# PushButtonGreen.net
KiCad netlist of a schematic drawn in Altium Designer
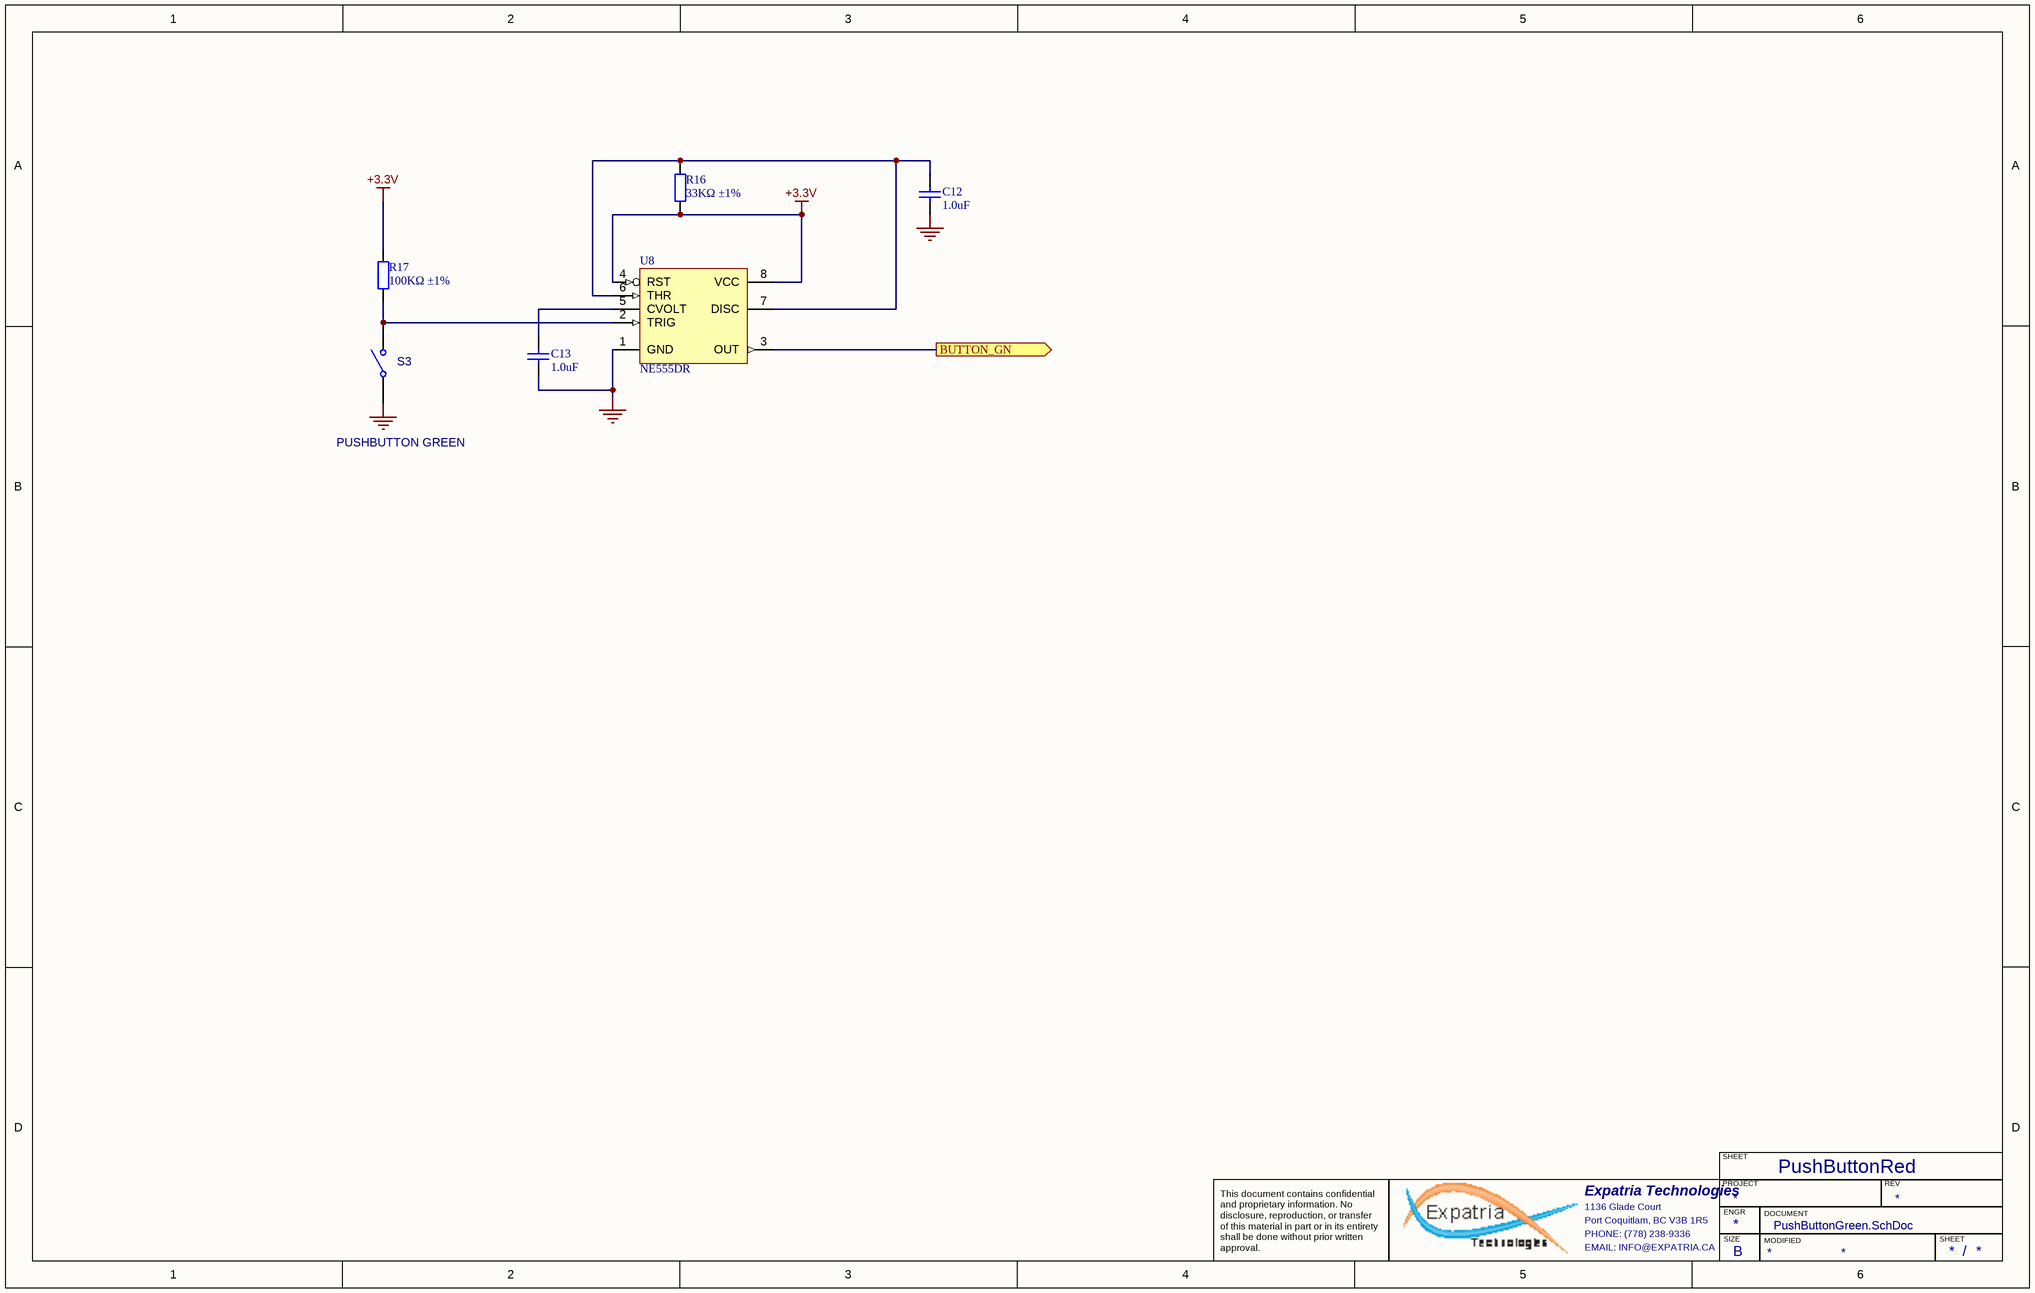
[diagram p0: PushButtonGreen.SchDoc]

(export (version "E")
  (design (tool "Eeschema 10.0.6"))
  (components
    (comp (ref "C12")
      (value "1.0uF")
      (footprint "0402_C")
      (description "Chip capacitor")
      (fields
        (field (name "MANUFACTURER") "Samsung Electro-Mechanics")
        (field (name "PARTNUMBER") "CL05A105KA5NQNC")
      )
      (libsource (lib "Cap") (part "0402 1.0uF (105) 10% 25V"))
    )
    (comp (ref "C13")
      (value "1.0uF")
      (footprint "0402_C")
      (description "Chip capacitor")
      (fields
        (field (name "MANUFACTURER") "Samsung Electro-Mechanics")
        (field (name "PARTNUMBER") "CL05A105KA5NQNC")
      )
      (libsource (lib "Cap") (part "0402 1.0uF (105) 10% 25V"))
    )
    (comp (ref "R16")
      (value "33KΩ ±1%")
      (footprint "0402_R")
      (description "Chip resistor")
      (fields (field (name "MANUFACTURER") "Uniroyal Elec") (field (name "PARTNUMBER") "0402WGF3302TCE"))
      (libsource (lib "RES") (part "0402 33K (3302) 1%"))
    )
    (comp (ref "R17")
      (value "100KΩ ±1%")
      (footprint "0402_R")
      (description "Chip resistor")
      (fields (field (name "MANUFACTURER") "Uniroyal Elec") (field (name "PARTNUMBER") "0402WGF1003TCE"))
      (libsource (lib "RES") (part "0402 100K (1003) 1%"))
    )
    (comp (ref "S3")
      (value "PUSHBUTTON GREEN")
      (footprint "D6C10F1LFS _GREEN")
      (description "SWITCH PUSH SPST-NO 0.1A 32V RED")
      (libsource (lib "bluebell") (part "D6R40 F1 LFS"))
    )
    (comp (ref "U8")
      (value "NE555DR")
      (footprint "SOIC-8_150mil")
      (description "时基集成")
      (libsource (lib "IC") (part "NE555DR_[C7593]"))
    )
  )
  (nets
    (net (code "1") (name "+3.3V") (class "Default")
      (node (ref "R16") (pin "1") (pinfunction "1_1") (pintype "passive"))
      (node (ref "R17") (pin "2") (pinfunction "2_2") (pintype "passive"))
      (node (ref "U8") (pin "4") (pinfunction "RST_4") (pintype "input"))
      (node (ref "U8") (pin "8") (pinfunction "VCC_8") (pintype "power_in"))
    )
    (net (code "2") (name "/BUTTON_GN") (class "Default")
      (node (ref "U8") (pin "3") (pinfunction "OUT_3") (pintype "output"))
    )
    (net (code "3") (name "GND") (class "Default")
      (node (ref "C12") (pin "1") (pinfunction "1_1") (pintype "passive"))
      (node (ref "C13") (pin "2") (pinfunction "2_2") (pintype "passive"))
      (node (ref "S3") (pin "1") (pinfunction "COMMON_1") (pintype "passive"))
      (node (ref "U8") (pin "1") (pinfunction "GND_1") (pintype "power_in"))
    )
    (net (code "4") (name "Net-(S3-NO)") (class "Default")
      (node (ref "R17") (pin "1") (pinfunction "1_1") (pintype "passive"))
      (node (ref "S3") (pin "2") (pinfunction "NO_2") (pintype "passive"))
      (node (ref "U8") (pin "2") (pinfunction "TRIG_2") (pintype "input"))
    )
    (net (code "5") (name "Net-(U8-CVOLT)") (class "Default")
      (node (ref "C13") (pin "1") (pinfunction "1_1") (pintype "passive"))
      (node (ref "U8") (pin "5") (pinfunction "CVOLT_5") (pintype "passive"))
    )
    (net (code "6") (name "Net-(U8-DISC)") (class "Default")
      (node (ref "C12") (pin "2") (pinfunction "2_2") (pintype "passive"))
      (node (ref "R16") (pin "2") (pinfunction "2_2") (pintype "passive"))
      (node (ref "U8") (pin "6") (pinfunction "THR_6") (pintype "input"))
      (node (ref "U8") (pin "7") (pinfunction "DISC_7") (pintype "open_collector"))
    )
  )
)
